# Load_Testbed_V3.net
KiCad netlist of a schematic drawn in EAGLE
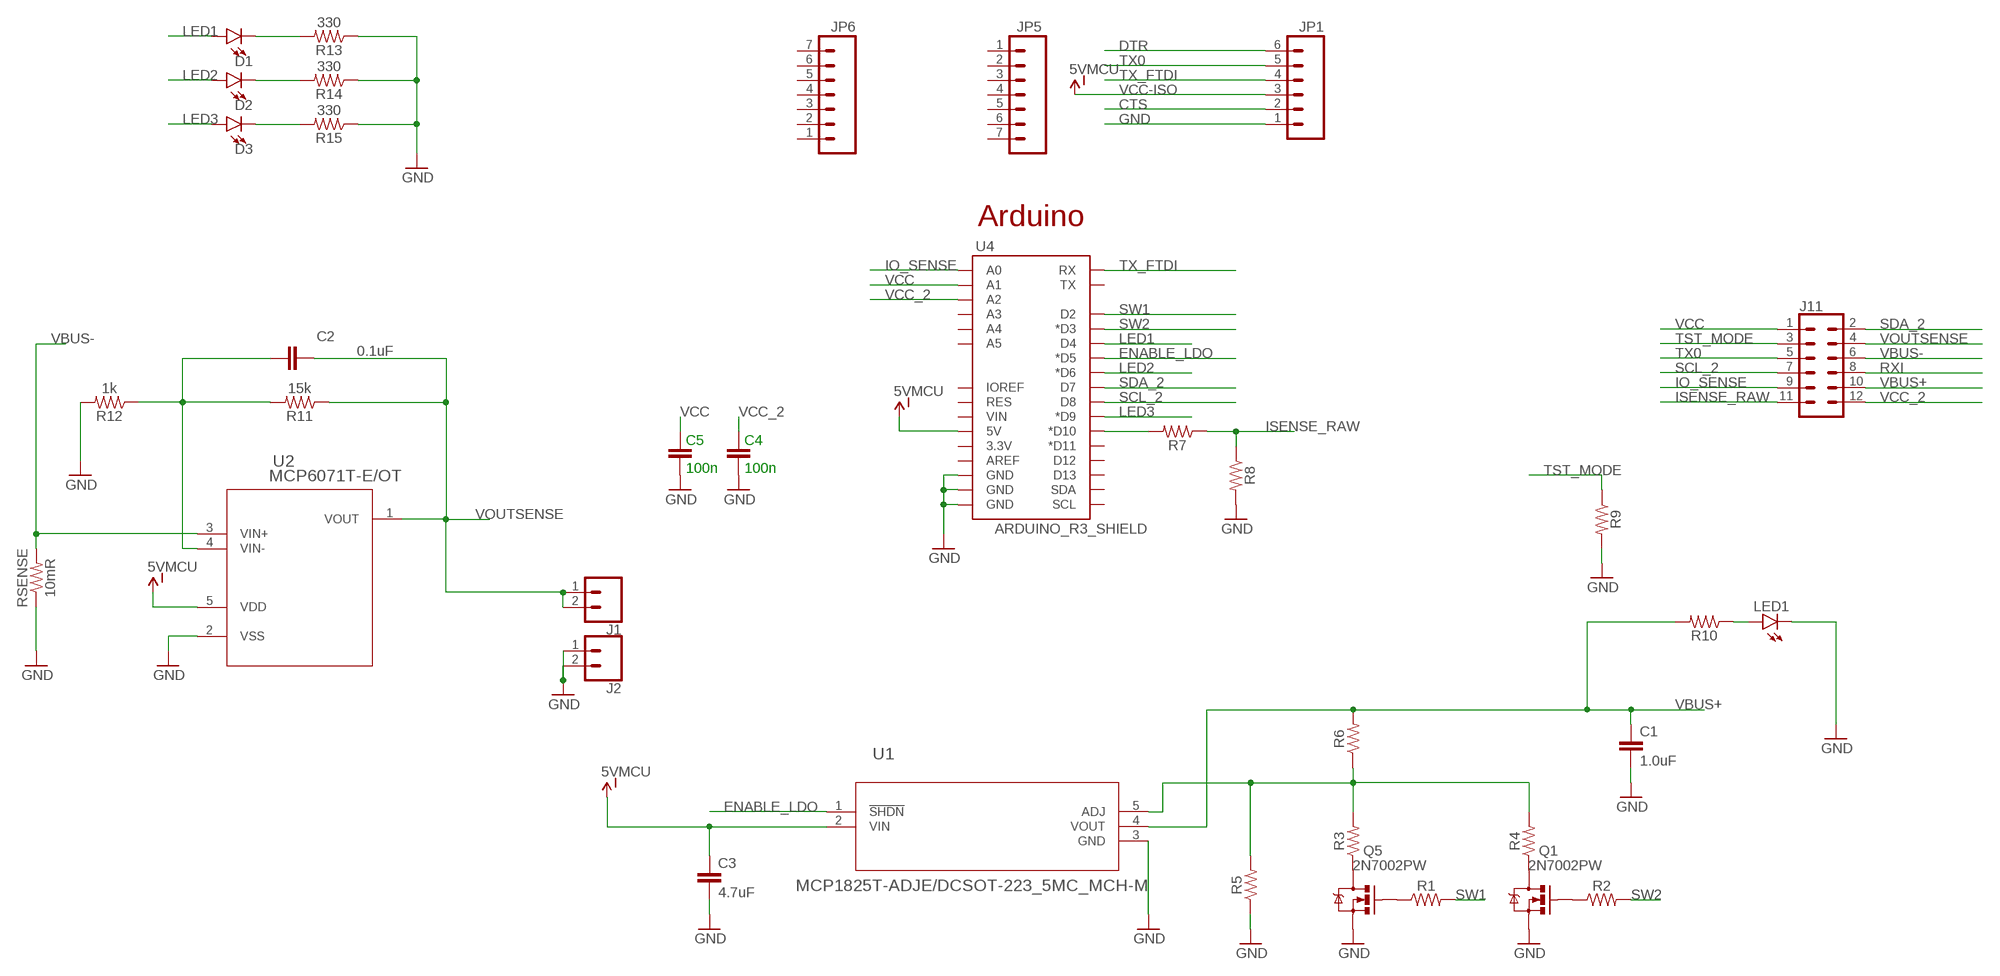
[diagram p0: schematic, sheet 1]

(export (version "E")
  (design (tool "Eeschema 10.0.6"))
  (components
    (comp (ref "C1")
      (value "1.0uF")
      (footprint "eagle-import:0805")
      (libsource (lib "eagle-import") (part "1.0UF-0805-25V-(+80/-20%)"))
    )
    (comp (ref "C2")
      (value "0.1uF")
      (footprint "eagle-import:0603")
      (libsource (lib "eagle-import") (part "0.1UF-0603-25V-(+80/-20%)"))
    )
    (comp (ref "C3")
      (value "4.7uF")
      (footprint "eagle-import:0603")
      (libsource (lib "eagle-import") (part "4.7UF0603"))
    )
    (comp (ref "C4")
      (value "100n")
      (footprint "eagle-import:0805")
      (libsource (lib "eagle-import") (part "CAP0805"))
    )
    (comp (ref "C5")
      (value "100n")
      (footprint "eagle-import:0805")
      (libsource (lib "eagle-import") (part "CAP0805"))
    )
    (comp (ref "D1")
      (value "LED1206")
      (footprint "eagle-import:LED-1206")
      (libsource (lib "eagle-import") (part "LED1206"))
    )
    (comp (ref "D2")
      (value "LED1206")
      (footprint "eagle-import:LED-1206")
      (libsource (lib "eagle-import") (part "LED1206"))
    )
    (comp (ref "D3")
      (value "LED1206")
      (footprint "eagle-import:LED-1206")
      (libsource (lib "eagle-import") (part "LED1206"))
    )
    (comp (ref "J1")
      (value "CONN_02")
      (footprint "eagle-import:1X02")
      (libsource (lib "eagle-import") (part "CONN_02"))
    )
    (comp (ref "J2")
      (value "CONN_02")
      (footprint "eagle-import:1X02")
      (libsource (lib "eagle-import") (part "CONN_02"))
    )
    (comp (ref "J11")
      (value "2X6 FEMALE")
      (footprint "eagle-import:2X6")
      (libsource (lib "eagle-import") (part "CONN_06X2PTH_FEMALE"))
    )
    (comp (ref "JP1")
      (value "M06NO_SILK_FEMALE_PTH")
      (footprint "eagle-import:1X06_NO_SILK")
      (libsource (lib "eagle-import") (part "M06NO_SILK_FEMALE_PTH"))
    )
    (comp (ref "JP5")
      (value "M07NO_SILK")
      (footprint "eagle-import:1X07_NO_SILK")
      (libsource (lib "eagle-import") (part "M07NO_SILK"))
    )
    (comp (ref "JP6")
      (value "M07NO_SILK")
      (footprint "eagle-import:1X07_NO_SILK")
      (libsource (lib "eagle-import") (part "M07NO_SILK"))
    )
    (comp (ref "LED1")
      (value "LED3MM")
      (footprint "eagle-import:LED3MM")
      (libsource (lib "eagle-import") (part "led_259_LED3MM"))
    )
    (comp (ref "Q1")
      (value "2N7002PW")
      (footprint "eagle-import:SOT323")
      (libsource (lib "eagle-import") (part "MOSFET-NCHANNEL2N7002PW"))
    )
    (comp (ref "Q5")
      (value "2N7002PW")
      (footprint "eagle-import:SOT323")
      (libsource (lib "eagle-import") (part "MOSFET-NCHANNEL2N7002PW"))
    )
    (comp (ref "R1")
      (value "RESISTOR0805")
      (footprint "eagle-import:0805")
      (libsource (lib "eagle-import") (part "RESISTOR0805"))
    )
    (comp (ref "R2")
      (value "RESISTOR0805")
      (footprint "eagle-import:0805")
      (libsource (lib "eagle-import") (part "RESISTOR0805"))
    )
    (comp (ref "R3")
      (value "RESISTOR0805")
      (footprint "eagle-import:0805")
      (libsource (lib "eagle-import") (part "RESISTOR0805"))
    )
    (comp (ref "R4")
      (value "RESISTOR0805")
      (footprint "eagle-import:0805")
      (libsource (lib "eagle-import") (part "RESISTOR0805"))
    )
    (comp (ref "R5")
      (value "RESISTOR0805")
      (footprint "eagle-import:0805")
      (libsource (lib "eagle-import") (part "RESISTOR0805"))
    )
    (comp (ref "R6")
      (value "RESISTOR0805")
      (footprint "eagle-import:0805")
      (libsource (lib "eagle-import") (part "RESISTOR0805"))
    )
    (comp (ref "R7")
      (value "RESISTOR0805")
      (footprint "eagle-import:0805")
      (libsource (lib "eagle-import") (part "RESISTOR0805"))
    )
    (comp (ref "R8")
      (value "RESISTOR0805")
      (footprint "eagle-import:0805")
      (libsource (lib "eagle-import") (part "RESISTOR0805"))
    )
    (comp (ref "R9")
      (value "RESISTOR0805")
      (footprint "eagle-import:0805")
      (libsource (lib "eagle-import") (part "RESISTOR0805"))
    )
    (comp (ref "R10")
      (value "RESISTOR0805")
      (footprint "eagle-import:0805")
      (libsource (lib "eagle-import") (part "RESISTOR0805"))
    )
    (comp (ref "R11")
      (value "15k")
      (footprint "eagle-import:0402")
      (libsource (lib "eagle-import") (part "RESISTOR0402"))
    )
    (comp (ref "R12")
      (value "1k")
      (footprint "eagle-import:0402")
      (libsource (lib "eagle-import") (part "RESISTOR0402"))
    )
    (comp (ref "R13")
      (value "330")
      (footprint "eagle-import:0805")
      (libsource (lib "eagle-import") (part "RESISTOR0805"))
    )
    (comp (ref "R14")
      (value "330")
      (footprint "eagle-import:0805")
      (libsource (lib "eagle-import") (part "RESISTOR0805"))
    )
    (comp (ref "R15")
      (value "330")
      (footprint "eagle-import:0805")
      (libsource (lib "eagle-import") (part "RESISTOR0805"))
    )
    (comp (ref "RSENSE")
      (value "10mR")
      (footprint "eagle-import:0603")
      (libsource (lib "eagle-import") (part "RESISTOR0603"))
    )
    (comp (ref "U1")
      (value "MCP1825T-ADJE/DCSOT-223_5MC_MCH-M")
      (footprint "eagle-import:SOT-223_5MC_MCH-M")
      (fields (field (name "MANUFACTURER_PART_NUMBER") "MCP1825T-ADJE/DC"))
      (libsource (lib "eagle-import") (part "MCP1825T-ADJE/DCSOT-223_5MC_MCH-M"))
    )
    (comp (ref "U2")
      (value "MCP6071T-E/OT")
      (footprint "eagle-import:SOT-23-5_MC_MCH")
      (fields (field (name "COPYRIGHT") "Copyright (C) 2018 Accelerated Designs. All rights reserved"))
      (libsource (lib "eagle-import") (part "MCP6071T-E/OT"))
    )
    (comp (ref "U4")
      (value "ARDUINO_R3_SHIELD")
      (footprint "eagle-import:UNO_R3_SHIELD")
      (libsource (lib "eagle-import") (part "ARDUINO_R3_SHIELD"))
    )
  )
  (nets
    (net (code "1") (name "/CTS") (class "Default")
      (node (ref "JP1") (pin "2") (pinfunction "2_2") (pintype "passive"))
    )
    (net (code "2") (name "/DTR") (class "Default")
      (node (ref "JP1") (pin "6") (pinfunction "6_6") (pintype "passive"))
    )
    (net (code "3") (name "/ENABLE_LDO") (class "Default")
      (node (ref "U1") (pin "1") (pinfunction "~{SHDN}_1") (pintype "passive"))
      (node (ref "U4") (pin "D5") (pinfunction "*D5_D5") (pintype "bidirectional"))
    )
    (net (code "4") (name "/IO_SENSE") (class "Default")
      (node (ref "J11") (pin "9") (pinfunction "9_9") (pintype "passive"))
      (node (ref "U4") (pin "A0") (pinfunction "A0_A0") (pintype "bidirectional"))
    )
    (net (code "5") (name "/ISENSE_RAW") (class "Default")
      (node (ref "J11") (pin "11") (pinfunction "11_11") (pintype "passive"))
      (node (ref "R7") (pin "1") (pinfunction "1_1") (pintype "passive"))
      (node (ref "R8") (pin "1") (pinfunction "1_1") (pintype "passive"))
    )
    (net (code "6") (name "/LED1") (class "Default")
      (node (ref "D1") (pin "A") (pinfunction "A_A") (pintype "passive"))
      (node (ref "U4") (pin "D4") (pinfunction "D4_D4") (pintype "bidirectional"))
    )
    (net (code "7") (name "/LED2") (class "Default")
      (node (ref "D2") (pin "A") (pinfunction "A_A") (pintype "passive"))
      (node (ref "U4") (pin "D6") (pinfunction "*D6_D6") (pintype "bidirectional"))
    )
    (net (code "8") (name "/LED3") (class "Default")
      (node (ref "D3") (pin "A") (pinfunction "A_A") (pintype "passive"))
      (node (ref "U4") (pin "D9") (pinfunction "*D9_D9") (pintype "bidirectional"))
    )
    (net (code "9") (name "/RXI") (class "Default")
      (node (ref "J11") (pin "8") (pinfunction "8_8") (pintype "passive"))
    )
    (net (code "10") (name "/SCL_2") (class "Default")
      (node (ref "J11") (pin "7") (pinfunction "7_7") (pintype "passive"))
      (node (ref "U4") (pin "D8") (pinfunction "D8_D8") (pintype "bidirectional"))
    )
    (net (code "11") (name "/SDA_2") (class "Default")
      (node (ref "J11") (pin "2") (pinfunction "2_2") (pintype "passive"))
      (node (ref "U4") (pin "D7") (pinfunction "D7_D7") (pintype "bidirectional"))
    )
    (net (code "12") (name "/SW1") (class "Default")
      (node (ref "R1") (pin "2") (pinfunction "2_2") (pintype "passive"))
      (node (ref "U4") (pin "D2") (pinfunction "D2_D2") (pintype "bidirectional"))
    )
    (net (code "13") (name "/SW2") (class "Default")
      (node (ref "R2") (pin "2") (pinfunction "2_2") (pintype "passive"))
      (node (ref "U4") (pin "D3") (pinfunction "*D3_D3") (pintype "bidirectional"))
    )
    (net (code "14") (name "/TST_MODE") (class "Default")
      (node (ref "J11") (pin "3") (pinfunction "3_3") (pintype "passive"))
      (node (ref "R9") (pin "1") (pinfunction "1_1") (pintype "passive"))
    )
    (net (code "15") (name "/TX0") (class "Default")
      (node (ref "J11") (pin "5") (pinfunction "5_5") (pintype "passive"))
      (node (ref "JP1") (pin "5") (pinfunction "5_5") (pintype "passive"))
    )
    (net (code "16") (name "/TX_FTDI") (class "Default")
      (node (ref "JP1") (pin "4") (pinfunction "4_4") (pintype "passive"))
      (node (ref "U4") (pin "RX") (pinfunction "RX_RX") (pintype "bidirectional"))
    )
    (net (code "17") (name "/VBUS+") (class "Default")
      (node (ref "C1") (pin "1") (pinfunction "1_1") (pintype "passive"))
      (node (ref "J11") (pin "10") (pinfunction "10_10") (pintype "passive"))
      (node (ref "R10") (pin "2") (pinfunction "2_2") (pintype "passive"))
      (node (ref "R6") (pin "2") (pinfunction "2_2") (pintype "passive"))
      (node (ref "U1") (pin "4") (pinfunction "VOUT_4") (pintype "passive"))
    )
    (net (code "18") (name "/VBUS-") (class "Default")
      (node (ref "J11") (pin "6") (pinfunction "6_6") (pintype "passive"))
      (node (ref "RSENSE") (pin "2") (pinfunction "2_2") (pintype "passive"))
      (node (ref "U2") (pin "3") (pinfunction "VIN+_3") (pintype "input"))
    )
    (net (code "19") (name "/VCC") (class "Default")
      (node (ref "C5") (pin "2") (pinfunction "2_2") (pintype "passive"))
      (node (ref "J11") (pin "1") (pinfunction "1_1") (pintype "passive"))
      (node (ref "U4") (pin "A1") (pinfunction "A1_A1") (pintype "bidirectional"))
    )
    (net (code "20") (name "/VCC_2") (class "Default")
      (node (ref "C4") (pin "2") (pinfunction "2_2") (pintype "passive"))
      (node (ref "J11") (pin "12") (pinfunction "12_12") (pintype "passive"))
      (node (ref "U4") (pin "A2") (pinfunction "A2_A2") (pintype "bidirectional"))
    )
    (net (code "21") (name "/VOUTSENSE") (class "Default")
      (node (ref "C2") (pin "1") (pinfunction "1_1") (pintype "passive"))
      (node (ref "J1") (pin "1") (pinfunction "1_1") (pintype "passive"))
      (node (ref "J1") (pin "2") (pinfunction "2_2") (pintype "passive"))
      (node (ref "J11") (pin "4") (pinfunction "4_4") (pintype "passive"))
      (node (ref "R11") (pin "1") (pinfunction "1_1") (pintype "passive"))
      (node (ref "U2") (pin "1") (pinfunction "VOUT_1") (pintype "output"))
    )
    (net (code "22") (name "5VMCU") (class "Default")
      (node (ref "C3") (pin "1") (pinfunction "1_1") (pintype "passive"))
      (node (ref "JP1") (pin "3") (pinfunction "3_3") (pintype "passive"))
      (node (ref "U1") (pin "2") (pinfunction "VIN_2") (pintype "passive"))
      (node (ref "U2") (pin "5") (pinfunction "VDD_5") (pintype "power_in"))
      (node (ref "U4") (pin "5V") (pinfunction "5V_5V") (pintype "bidirectional"))
    )
    (net (code "23") (name "GND") (class "Default")
      (node (ref "C1") (pin "2") (pinfunction "2_2") (pintype "passive"))
      (node (ref "C3") (pin "2") (pinfunction "2_2") (pintype "passive"))
      (node (ref "C4") (pin "1") (pinfunction "1_1") (pintype "passive"))
      (node (ref "C5") (pin "1") (pinfunction "1_1") (pintype "passive"))
      (node (ref "J2") (pin "1") (pinfunction "1_1") (pintype "passive"))
      (node (ref "J2") (pin "2") (pinfunction "2_2") (pintype "passive"))
      (node (ref "JP1") (pin "1") (pinfunction "1_1") (pintype "passive"))
      (node (ref "LED1") (pin "K") (pinfunction "C_K") (pintype "passive"))
      (node (ref "Q1") (pin "2") (pinfunction "S_2") (pintype "passive"))
      (node (ref "Q5") (pin "2") (pinfunction "S_2") (pintype "passive"))
      (node (ref "R12") (pin "2") (pinfunction "2_2") (pintype "passive"))
      (node (ref "R13") (pin "1") (pinfunction "1_1") (pintype "passive"))
      (node (ref "R14") (pin "1") (pinfunction "1_1") (pintype "passive"))
      (node (ref "R15") (pin "1") (pinfunction "1_1") (pintype "passive"))
      (node (ref "R5") (pin "1") (pinfunction "1_1") (pintype "passive"))
      (node (ref "R8") (pin "2") (pinfunction "2_2") (pintype "passive"))
      (node (ref "R9") (pin "2") (pinfunction "2_2") (pintype "passive"))
      (node (ref "RSENSE") (pin "1") (pinfunction "1_1") (pintype "passive"))
      (node (ref "U1") (pin "3") (pinfunction "GND_3") (pintype "passive"))
      (node (ref "U2") (pin "2") (pinfunction "VSS_2") (pintype "power_in"))
      (node (ref "U4") (pin "GND@0") (pinfunction "GND_GND@0") (pintype "bidirectional"))
      (node (ref "U4") (pin "GND@1") (pinfunction "GND_GND@1") (pintype "bidirectional"))
      (node (ref "U4") (pin "GND@2") (pinfunction "GND_GND@2") (pintype "bidirectional"))
    )
    (net (code "24") (name "Net-(D1-PadC)") (class "Default")
      (node (ref "D1") (pin "C") (pinfunction "C_C") (pintype "passive"))
      (node (ref "R13") (pin "2") (pinfunction "2_2") (pintype "passive"))
    )
    (net (code "25") (name "Net-(D2-PadC)") (class "Default")
      (node (ref "D2") (pin "C") (pinfunction "C_C") (pintype "passive"))
      (node (ref "R14") (pin "2") (pinfunction "2_2") (pintype "passive"))
    )
    (net (code "26") (name "Net-(D3-PadC)") (class "Default")
      (node (ref "D3") (pin "C") (pinfunction "C_C") (pintype "passive"))
      (node (ref "R15") (pin "2") (pinfunction "2_2") (pintype "passive"))
    )
    (net (code "27") (name "Net-(LED1-PadA)") (class "Default")
      (node (ref "LED1") (pin "A") (pinfunction "A_A") (pintype "passive"))
      (node (ref "R10") (pin "1") (pinfunction "1_1") (pintype "passive"))
    )
    (net (code "28") (name "Net-(Q1-D)") (class "Default")
      (node (ref "Q1") (pin "3") (pinfunction "D_3") (pintype "passive"))
      (node (ref "R4") (pin "1") (pinfunction "1_1") (pintype "passive"))
    )
    (net (code "29") (name "Net-(Q1-G)") (class "Default")
      (node (ref "Q1") (pin "1") (pinfunction "G_1") (pintype "passive"))
      (node (ref "R2") (pin "1") (pinfunction "1_1") (pintype "passive"))
    )
    (net (code "30") (name "Net-(Q5-D)") (class "Default")
      (node (ref "Q5") (pin "3") (pinfunction "D_3") (pintype "passive"))
      (node (ref "R3") (pin "1") (pinfunction "1_1") (pintype "passive"))
    )
    (net (code "31") (name "Net-(Q5-G)") (class "Default")
      (node (ref "Q5") (pin "1") (pinfunction "G_1") (pintype "passive"))
      (node (ref "R1") (pin "1") (pinfunction "1_1") (pintype "passive"))
    )
    (net (code "32") (name "Net-(U1-ADJ)") (class "Default")
      (node (ref "R3") (pin "2") (pinfunction "2_2") (pintype "passive"))
      (node (ref "R4") (pin "2") (pinfunction "2_2") (pintype "passive"))
      (node (ref "R5") (pin "2") (pinfunction "2_2") (pintype "passive"))
      (node (ref "R6") (pin "1") (pinfunction "1_1") (pintype "passive"))
      (node (ref "U1") (pin "5") (pinfunction "ADJ_5") (pintype "passive"))
    )
    (net (code "33") (name "Net-(U2-VIN-)") (class "Default")
      (node (ref "C2") (pin "2") (pinfunction "2_2") (pintype "passive"))
      (node (ref "R11") (pin "2") (pinfunction "2_2") (pintype "passive"))
      (node (ref "R12") (pin "1") (pinfunction "1_1") (pintype "passive"))
      (node (ref "U2") (pin "4") (pinfunction "VIN-_4") (pintype "input"))
    )
    (net (code "34") (name "Net-(U4-*D10)") (class "Default")
      (node (ref "R7") (pin "2") (pinfunction "2_2") (pintype "passive"))
      (node (ref "U4") (pin "D10") (pinfunction "*D10_D10") (pintype "bidirectional"))
    )
    (net (code "35") (name "unconnected-(JP5-Pad1)") (class "Default")
      (node (ref "JP5") (pin "1") (pinfunction "1_1") (pintype "passive"))
    )
    (net (code "36") (name "unconnected-(JP5-Pad2)") (class "Default")
      (node (ref "JP5") (pin "2") (pinfunction "2_2") (pintype "passive"))
    )
    (net (code "37") (name "unconnected-(JP5-Pad3)") (class "Default")
      (node (ref "JP5") (pin "3") (pinfunction "3_3") (pintype "passive"))
    )
    (net (code "38") (name "unconnected-(JP5-Pad4)") (class "Default")
      (node (ref "JP5") (pin "4") (pinfunction "4_4") (pintype "passive"))
    )
    (net (code "39") (name "unconnected-(JP5-Pad5)") (class "Default")
      (node (ref "JP5") (pin "5") (pinfunction "5_5") (pintype "passive"))
    )
    (net (code "40") (name "unconnected-(JP5-Pad6)") (class "Default")
      (node (ref "JP5") (pin "6") (pinfunction "6_6") (pintype "passive"))
    )
    (net (code "41") (name "unconnected-(JP5-Pad7)") (class "Default")
      (node (ref "JP5") (pin "7") (pinfunction "7_7") (pintype "passive"))
    )
    (net (code "42") (name "unconnected-(JP6-Pad1)") (class "Default")
      (node (ref "JP6") (pin "1") (pinfunction "1_1") (pintype "passive"))
    )
    (net (code "43") (name "unconnected-(JP6-Pad2)") (class "Default")
      (node (ref "JP6") (pin "2") (pinfunction "2_2") (pintype "passive"))
    )
    (net (code "44") (name "unconnected-(JP6-Pad3)") (class "Default")
      (node (ref "JP6") (pin "3") (pinfunction "3_3") (pintype "passive"))
    )
    (net (code "45") (name "unconnected-(JP6-Pad4)") (class "Default")
      (node (ref "JP6") (pin "4") (pinfunction "4_4") (pintype "passive"))
    )
    (net (code "46") (name "unconnected-(JP6-Pad5)") (class "Default")
      (node (ref "JP6") (pin "5") (pinfunction "5_5") (pintype "passive"))
    )
    (net (code "47") (name "unconnected-(JP6-Pad6)") (class "Default")
      (node (ref "JP6") (pin "6") (pinfunction "6_6") (pintype "passive"))
    )
    (net (code "48") (name "unconnected-(JP6-Pad7)") (class "Default")
      (node (ref "JP6") (pin "7") (pinfunction "7_7") (pintype "passive"))
    )
    (net (code "49") (name "unconnected-(U4-*D11-PadD11)") (class "Default")
      (node (ref "U4") (pin "D11") (pinfunction "*D11_D11") (pintype "bidirectional"))
    )
    (net (code "50") (name "unconnected-(U4-Pad3.3V)") (class "Default")
      (node (ref "U4") (pin "3.3V") (pinfunction "3.3V_3.3V") (pintype "bidirectional"))
    )
    (net (code "51") (name "unconnected-(U4-PadA3)") (class "Default")
      (node (ref "U4") (pin "A3") (pinfunction "A3_A3") (pintype "bidirectional"))
    )
    (net (code "52") (name "unconnected-(U4-PadA4)") (class "Default")
      (node (ref "U4") (pin "A4") (pinfunction "A4_A4") (pintype "bidirectional"))
    )
    (net (code "53") (name "unconnected-(U4-PadA5)") (class "Default")
      (node (ref "U4") (pin "A5") (pinfunction "A5_A5") (pintype "bidirectional"))
    )
    (net (code "54") (name "unconnected-(U4-PadAREF)") (class "Default")
      (node (ref "U4") (pin "AREF") (pinfunction "AREF_AREF") (pintype "bidirectional"))
    )
    (net (code "55") (name "unconnected-(U4-PadD12)") (class "Default")
      (node (ref "U4") (pin "D12") (pinfunction "D12_D12") (pintype "bidirectional"))
    )
    (net (code "56") (name "unconnected-(U4-PadD13)") (class "Default")
      (node (ref "U4") (pin "D13") (pinfunction "D13_D13") (pintype "bidirectional"))
    )
    (net (code "57") (name "unconnected-(U4-PadIOREF)") (class "Default")
      (node (ref "U4") (pin "IOREF") (pinfunction "IOREF_IOREF") (pintype "bidirectional"))
    )
    (net (code "58") (name "unconnected-(U4-PadRES)") (class "Default")
      (node (ref "U4") (pin "RES") (pinfunction "RES_RES") (pintype "bidirectional"))
    )
    (net (code "59") (name "unconnected-(U4-PadSCL)") (class "Default")
      (node (ref "U4") (pin "SCL") (pinfunction "SCL_SCL") (pintype "bidirectional"))
    )
    (net (code "60") (name "unconnected-(U4-PadSDA)") (class "Default")
      (node (ref "U4") (pin "SDA") (pinfunction "SDA_SDA") (pintype "bidirectional"))
    )
    (net (code "61") (name "unconnected-(U4-PadTX)") (class "Default")
      (node (ref "U4") (pin "TX") (pinfunction "TX_TX") (pintype "bidirectional"))
    )
    (net (code "62") (name "unconnected-(U4-PadVIN)") (class "Default")
      (node (ref "U4") (pin "VIN") (pinfunction "VIN_VIN") (pintype "bidirectional"))
    )
  )
)
